# Review_PCD_1_4.net
KiCad netlist of a schematic drawn in EAGLE
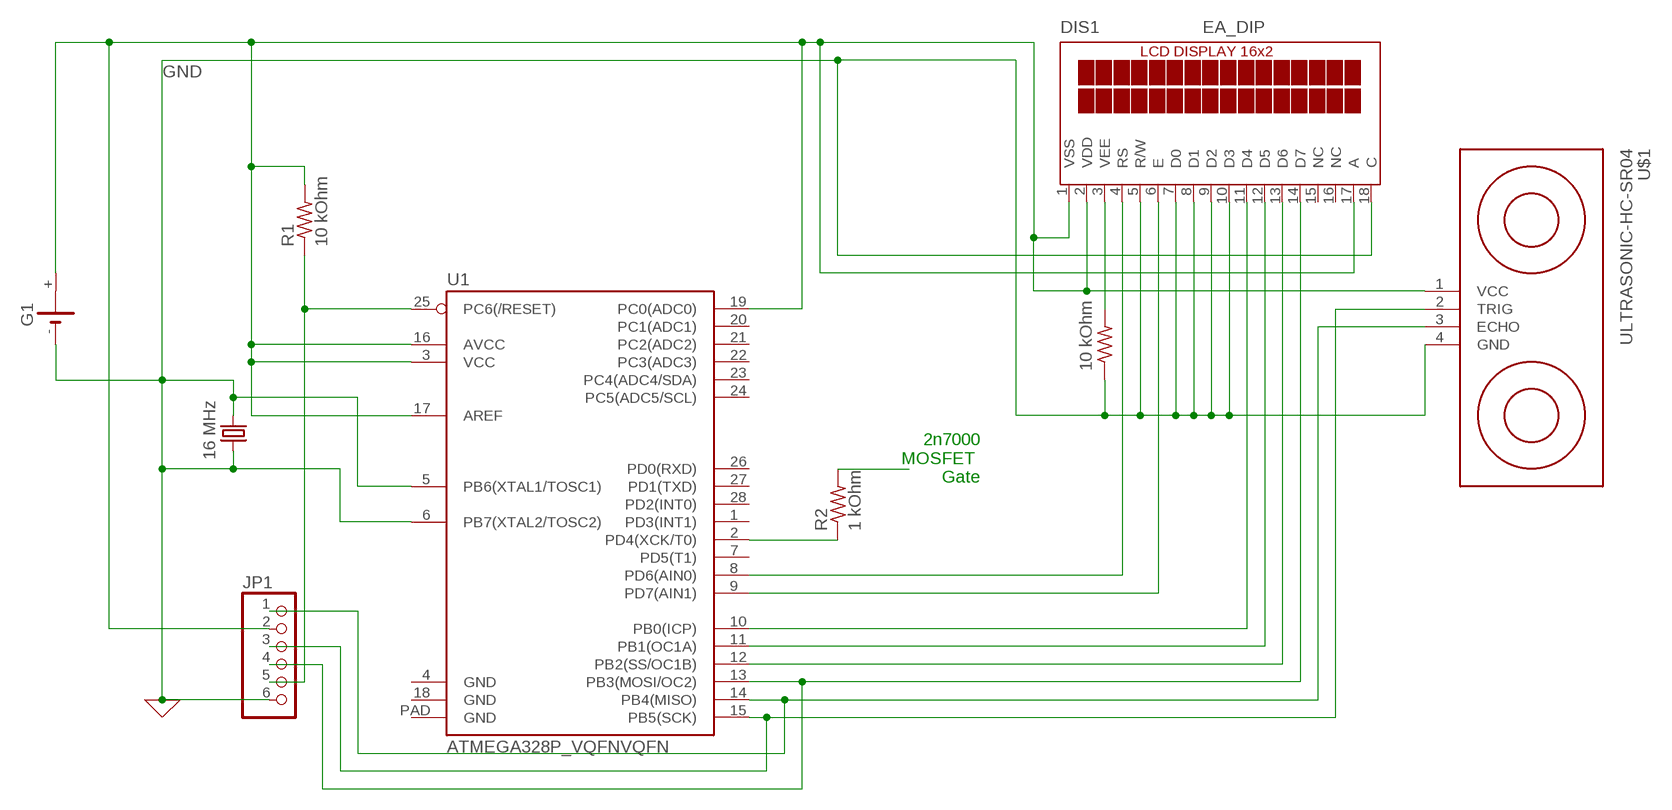
[diagram p0: schematic, sheet 1]

(export (version "E")
  (design (tool "Eeschema 10.0.6"))
  (components
    (comp (ref "DIS1")
      (value "EA_DIP")
      (footprint "eagle-import:EA_DIP")
      (libsource (lib "eagle-import") (part "EA_DIP"))
    )
    (comp (ref "G1")
      (value "CR1/2")
      (footprint "eagle-import:CR1_2")
      (libsource (lib "eagle-import") (part "CR1/2"))
    )
    (comp (ref "JP1")
      (value "PINHD-1X6-3.5MM")
      (footprint "eagle-import:1X06-3.5MM")
      (libsource (lib "eagle-import") (part "PINHD-1X6-3.5MM"))
    )
    (comp (ref "Q1")
      (value "16 MHz")
      (footprint "eagle-import:1.6X1.2")
      (fields (field (name "Q1") "16 MHz"))
      (libsource (lib "eagle-import") (part "KX-4"))
    )
    (comp (ref "R1")
      (value "10 kOhm")
      (footprint "eagle-import:R2012W")
      (libsource (lib "eagle-import") (part "R-US_R2012W"))
    )
    (comp (ref "R2")
      (value "1 kOhm")
      (footprint "eagle-import:R2012W")
      (fields (field (name "R1") "1 kOhm"))
      (libsource (lib "eagle-import") (part "R-US_R2012W"))
    )
    (comp (ref "R3")
      (value "10 kOhm")
      (footprint "eagle-import:R2012W")
      (fields (field (name "R1") "10 kOhm"))
      (libsource (lib "eagle-import") (part "R-US_R2012W"))
    )
    (comp (ref "U$1")
      (value "ULTRASONIC-HC-SR04")
      (footprint "eagle-import:ULTRASONIC-HC-SR04")
      (libsource (lib "eagle-import") (part "ULTRASONIC-HC-SR04"))
    )
    (comp (ref "U1")
      (value "ATMEGA328P_VQFNVQFN")
      (footprint "eagle-import:VQFN-28")
      (libsource (lib "eagle-import") (part "ATMEGA328P_VQFNVQFN"))
    )
  )
  (nets
    (net (code "1") (name "GND") (class "Default")
      (node (ref "DIS1") (pin "10") (pinfunction "D3_10") (pintype "input"))
      (node (ref "DIS1") (pin "18") (pinfunction "C_18") (pintype "passive"))
      (node (ref "DIS1") (pin "5") (pinfunction "R/W_5") (pintype "input"))
      (node (ref "DIS1") (pin "7") (pinfunction "D0_7") (pintype "input"))
      (node (ref "DIS1") (pin "8") (pinfunction "D1_8") (pintype "input"))
      (node (ref "DIS1") (pin "9") (pinfunction "D2_9") (pintype "input"))
      (node (ref "G1") (pin "-") (pinfunction "-_-") (pintype "passive"))
      (node (ref "JP1") (pin "6") (pinfunction "6_6") (pintype "passive"))
      (node (ref "Q1") (pin "1") (pinfunction "1_1") (pintype "passive"))
      (node (ref "Q1") (pin "3") (pinfunction "2_3") (pintype "passive"))
      (node (ref "R3") (pin "1") (pinfunction "1_1") (pintype "passive"))
      (node (ref "U$1") (pin "4") (pinfunction "GND_4") (pintype "power_in"))
      (node (ref "U1") (pin "5") (pinfunction "PB6(XTAL1/TOSC1)_5") (pintype "bidirectional"))
      (node (ref "U1") (pin "6") (pinfunction "PB7(XTAL2/TOSC2)_6") (pintype "bidirectional"))
    )
    (net (code "2") (name "Net-(DIS1-A)") (class "Default")
      (node (ref "DIS1") (pin "1") (pinfunction "VSS_1") (pintype "power_in"))
      (node (ref "DIS1") (pin "17") (pinfunction "A_17") (pintype "passive"))
      (node (ref "DIS1") (pin "2") (pinfunction "VDD_2") (pintype "power_in"))
      (node (ref "G1") (pin "+") (pinfunction "+_+") (pintype "passive"))
      (node (ref "JP1") (pin "2") (pinfunction "2_2") (pintype "passive"))
      (node (ref "R1") (pin "2") (pinfunction "2_2") (pintype "passive"))
      (node (ref "U$1") (pin "1") (pinfunction "VCC_1") (pintype "power_in"))
      (node (ref "U1") (pin "16") (pinfunction "AVCC_16") (pintype "bidirectional"))
      (node (ref "U1") (pin "17") (pinfunction "AREF_17") (pintype "bidirectional"))
      (node (ref "U1") (pin "19") (pinfunction "PC0(ADC0)_19") (pintype "bidirectional"))
      (node (ref "U1") (pin "3") (pinfunction "VCC_3") (pintype "bidirectional"))
    )
    (net (code "3") (name "Net-(DIS1-D4)") (class "Default")
      (node (ref "DIS1") (pin "11") (pinfunction "D4_11") (pintype "input"))
      (node (ref "U1") (pin "10") (pinfunction "PB0(ICP)_10") (pintype "bidirectional"))
    )
    (net (code "4") (name "Net-(DIS1-D5)") (class "Default")
      (node (ref "DIS1") (pin "12") (pinfunction "D5_12") (pintype "input"))
      (node (ref "U1") (pin "11") (pinfunction "PB1(OC1A)_11") (pintype "bidirectional"))
    )
    (net (code "5") (name "Net-(DIS1-D6)") (class "Default")
      (node (ref "DIS1") (pin "13") (pinfunction "D6_13") (pintype "input"))
      (node (ref "U1") (pin "12") (pinfunction "PB2(SS/OC1B)_12") (pintype "bidirectional"))
    )
    (net (code "6") (name "Net-(DIS1-D7)") (class "Default")
      (node (ref "DIS1") (pin "14") (pinfunction "D7_14") (pintype "input"))
      (node (ref "JP1") (pin "4") (pinfunction "4_4") (pintype "passive"))
      (node (ref "U1") (pin "13") (pinfunction "PB3(MOSI/OC2)_13") (pintype "bidirectional"))
    )
    (net (code "7") (name "Net-(DIS1-E)") (class "Default")
      (node (ref "DIS1") (pin "6") (pinfunction "E_6") (pintype "input"))
      (node (ref "U1") (pin "9") (pinfunction "PD7(AIN1)_9") (pintype "bidirectional"))
    )
    (net (code "8") (name "Net-(DIS1-RS)") (class "Default")
      (node (ref "DIS1") (pin "4") (pinfunction "RS_4") (pintype "input"))
      (node (ref "U1") (pin "8") (pinfunction "PD6(AIN0)_8") (pintype "bidirectional"))
    )
    (net (code "9") (name "Net-(DIS1-VEE)") (class "Default")
      (node (ref "DIS1") (pin "3") (pinfunction "VEE_3") (pintype "power_in"))
      (node (ref "R3") (pin "2") (pinfunction "2_2") (pintype "passive"))
    )
    (net (code "10") (name "Net-(U$1-ECHO)") (class "Default")
      (node (ref "JP1") (pin "1") (pinfunction "1_1") (pintype "passive"))
      (node (ref "U$1") (pin "3") (pinfunction "ECHO_3") (pintype "output"))
      (node (ref "U1") (pin "14") (pinfunction "PB4(MISO)_14") (pintype "bidirectional"))
    )
    (net (code "11") (name "Net-(U$1-TRIG)") (class "Default")
      (node (ref "JP1") (pin "3") (pinfunction "3_3") (pintype "passive"))
      (node (ref "U$1") (pin "2") (pinfunction "TRIG_2") (pintype "input"))
      (node (ref "U1") (pin "15") (pinfunction "PB5(SCK)_15") (pintype "bidirectional"))
    )
    (net (code "12") (name "Net-(U1-PC6({slash}RESET))") (class "Default")
      (node (ref "JP1") (pin "5") (pinfunction "5_5") (pintype "passive"))
      (node (ref "R1") (pin "1") (pinfunction "1_1") (pintype "passive"))
      (node (ref "U1") (pin "25") (pinfunction "PC6(/RESET)_25") (pintype "bidirectional"))
    )
    (net (code "13") (name "Net-(U1-PD4(XCK{slash}T0))") (class "Default")
      (node (ref "R2") (pin "1") (pinfunction "1_1") (pintype "passive"))
      (node (ref "U1") (pin "2") (pinfunction "PD4(XCK/T0)_2") (pintype "bidirectional"))
    )
    (net (code "14") (name "unconnected-(DIS1-NC-Pad15)") (class "Default")
      (node (ref "DIS1") (pin "15") (pinfunction "NC_15") (pintype "no_connect"))
    )
    (net (code "15") (name "unconnected-(DIS1-NC-Pad16)") (class "Default")
      (node (ref "DIS1") (pin "16") (pinfunction "NC_16") (pintype "no_connect"))
    )
    (net (code "16") (name "unconnected-(G1-+-Pad+@1)") (class "Default")
      (node (ref "G1") (pin "+@1") (pinfunction "+_+@1") (pintype "passive"))
    )
    (net (code "17") (name "unconnected-(R2-Pad2)") (class "Default")
      (node (ref "R2") (pin "2") (pinfunction "2_2") (pintype "passive"))
    )
    (net (code "18") (name "unconnected-(U1-GND-Pad4)") (class "Default")
      (node (ref "U1") (pin "4") (pinfunction "GND_4") (pintype "bidirectional"))
    )
    (net (code "19") (name "unconnected-(U1-GND-Pad18)") (class "Default")
      (node (ref "U1") (pin "18") (pinfunction "GND_18") (pintype "bidirectional"))
    )
    (net (code "20") (name "unconnected-(U1-GND-PadPAD)") (class "Default")
      (node (ref "U1") (pin "PAD") (pinfunction "GND_PAD") (pintype "bidirectional"))
    )
    (net (code "21") (name "unconnected-(U1-PC1(ADC1)-Pad20)") (class "Default")
      (node (ref "U1") (pin "20") (pinfunction "PC1(ADC1)_20") (pintype "bidirectional"))
    )
    (net (code "22") (name "unconnected-(U1-PC2(ADC2)-Pad21)") (class "Default")
      (node (ref "U1") (pin "21") (pinfunction "PC2(ADC2)_21") (pintype "bidirectional"))
    )
    (net (code "23") (name "unconnected-(U1-PC3(ADC3)-Pad22)") (class "Default")
      (node (ref "U1") (pin "22") (pinfunction "PC3(ADC3)_22") (pintype "bidirectional"))
    )
    (net (code "24") (name "unconnected-(U1-PC4(ADC4{slash}SDA)-Pad23)") (class "Default")
      (node (ref "U1") (pin "23") (pinfunction "PC4(ADC4/SDA)_23") (pintype "bidirectional"))
    )
    (net (code "25") (name "unconnected-(U1-PC5(ADC5{slash}SCL)-Pad24)") (class "Default")
      (node (ref "U1") (pin "24") (pinfunction "PC5(ADC5/SCL)_24") (pintype "bidirectional"))
    )
    (net (code "26") (name "unconnected-(U1-PD0(RXD)-Pad26)") (class "Default")
      (node (ref "U1") (pin "26") (pinfunction "PD0(RXD)_26") (pintype "bidirectional"))
    )
    (net (code "27") (name "unconnected-(U1-PD1(TXD)-Pad27)") (class "Default")
      (node (ref "U1") (pin "27") (pinfunction "PD1(TXD)_27") (pintype "bidirectional"))
    )
    (net (code "28") (name "unconnected-(U1-PD2(INT0)-Pad28)") (class "Default")
      (node (ref "U1") (pin "28") (pinfunction "PD2(INT0)_28") (pintype "bidirectional"))
    )
    (net (code "29") (name "unconnected-(U1-PD3(INT1)-Pad1)") (class "Default")
      (node (ref "U1") (pin "1") (pinfunction "PD3(INT1)_1") (pintype "bidirectional"))
    )
    (net (code "30") (name "unconnected-(U1-PD5(T1)-Pad7)") (class "Default")
      (node (ref "U1") (pin "7") (pinfunction "PD5(T1)_7") (pintype "bidirectional"))
    )
  )
)
